# Fingerprint_lock_1_4.net
KiCad netlist of a schematic drawn in EAGLE
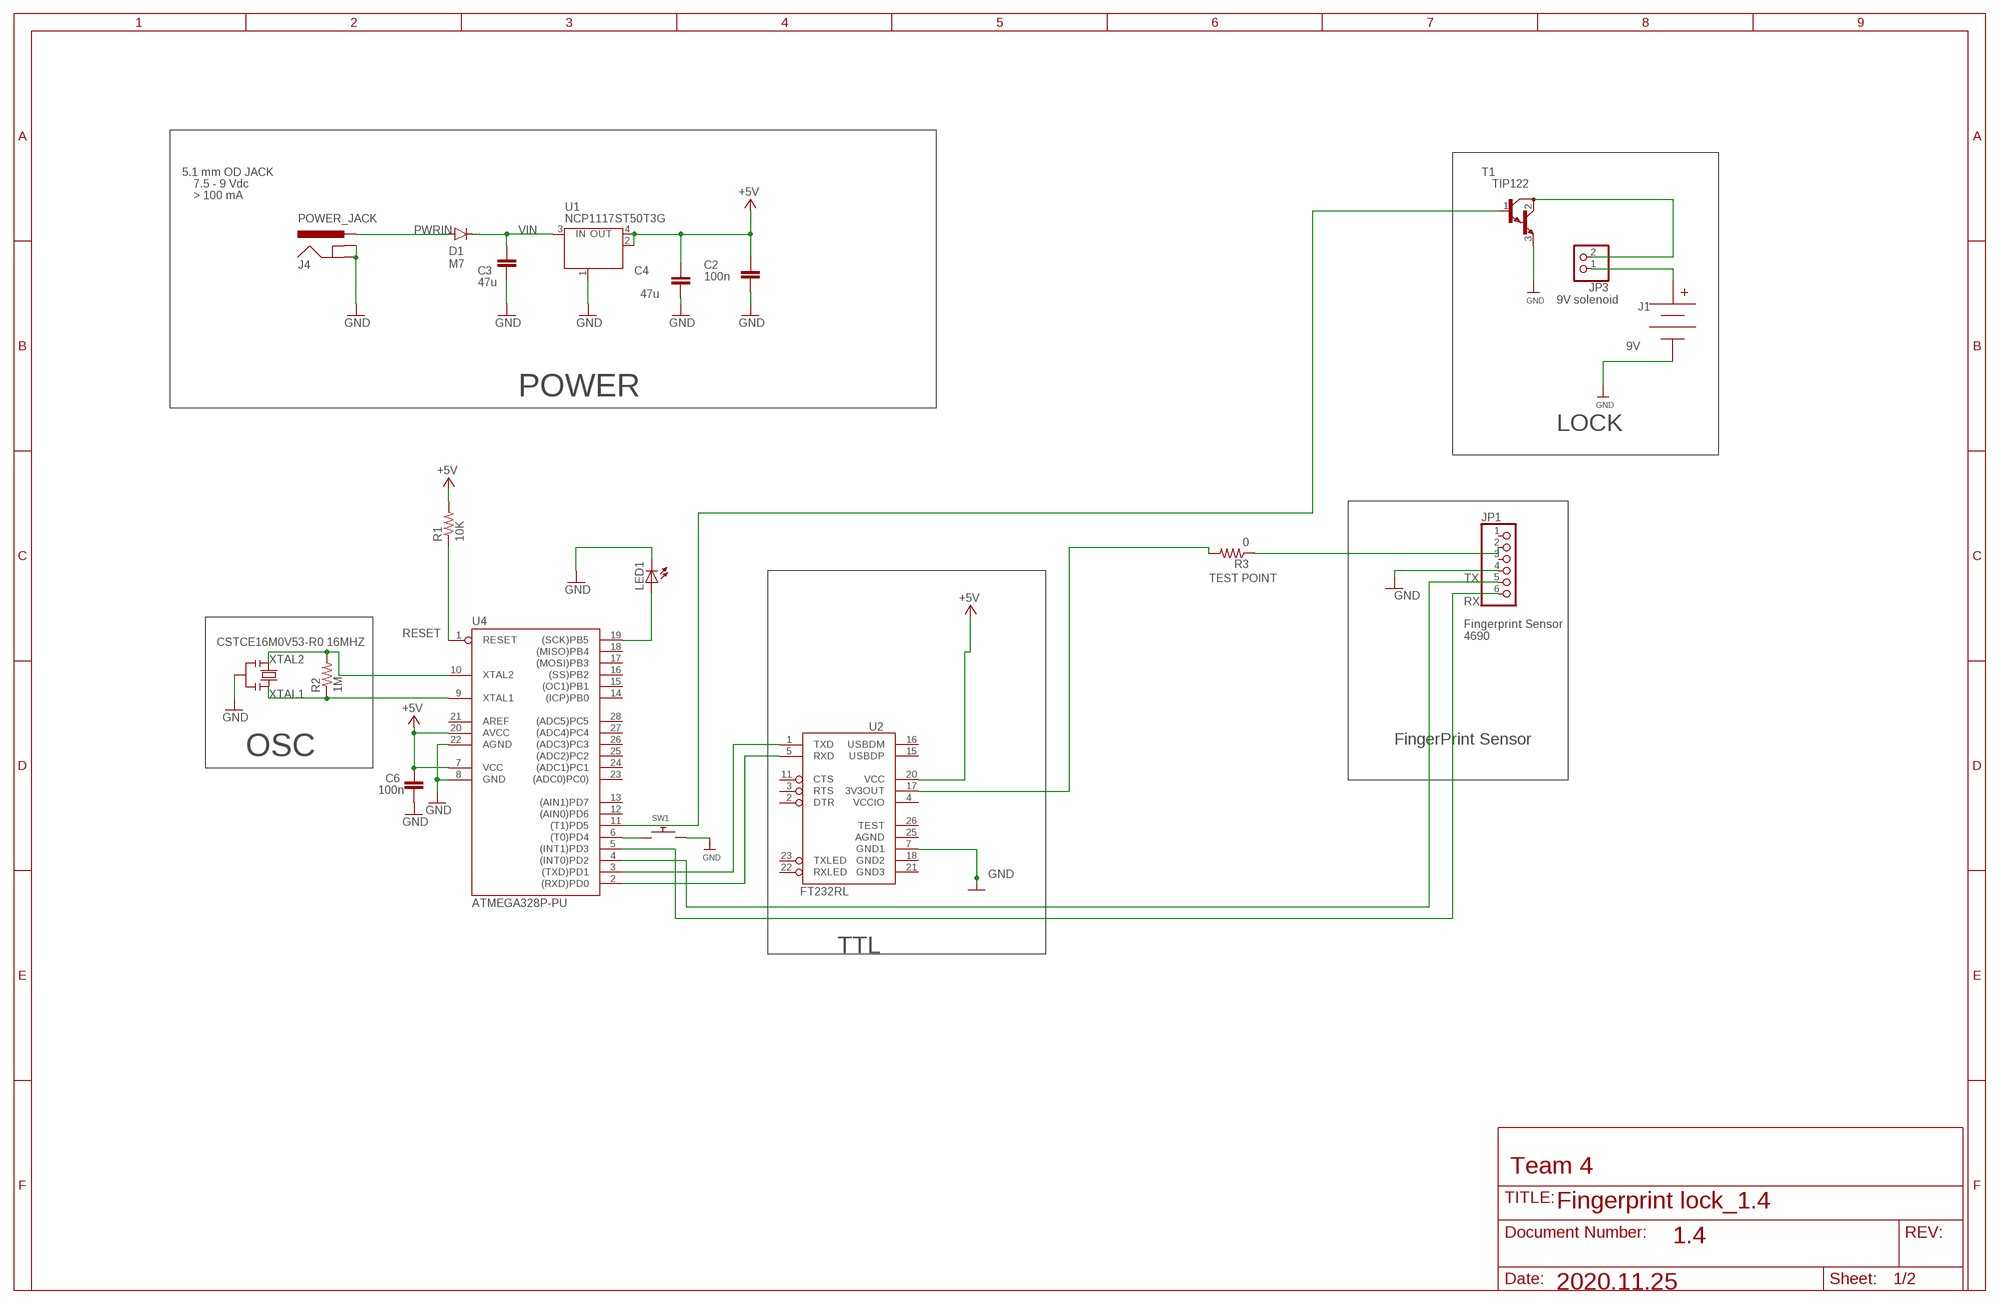
[diagram p0: schematic, sheet 1]

(export (version "E")
  (design (tool "Eeschema 10.0.6"))
  (components
    (comp (ref "C2")
      (value "100n")
      (footprint "eagle-import:C0805")
      (libsource (lib "eagle-import") (part "C-EUC0805"))
    )
    (comp (ref "C3")
      (value "47u")
      (footprint "eagle-import:C0805")
      (libsource (lib "eagle-import") (part "C-EUC0805"))
    )
    (comp (ref "C4")
      (value "47u")
      (footprint "eagle-import:C0805")
      (libsource (lib "eagle-import") (part "C-EUC0805"))
    )
    (comp (ref "C6")
      (value "100n")
      (footprint "eagle-import:C0805")
      (libsource (lib "eagle-import") (part "C-EUC0805"))
    )
    (comp (ref "D1")
      (value "M7")
      (footprint "eagle-import:SMB")
      (libsource (lib "eagle-import") (part "DIODE-SMB"))
    )
    (comp (ref "J1")
      (value "9V")
      (footprint "eagle-import:BC9VPC")
      (libsource (lib "eagle-import") (part "BC9VPC"))
    )
    (comp (ref "J4")
      (value "POWER_JACK")
      (footprint "eagle-import:POWER_JACK_PTH")
      (libsource (lib "eagle-import") (part "POWER_JACK"))
    )
    (comp (ref "JP1")
      (value "PINHD-1X6B")
      (footprint "eagle-import:1X06-BIG")
      (libsource (lib "eagle-import") (part "PINHD-1X6B"))
    )
    (comp (ref "JP3")
      (value "PINHD-1X2")
      (footprint "eagle-import:1X02")
      (libsource (lib "eagle-import") (part "PINHD-1X2"))
    )
    (comp (ref "LED1")
      (value "LEDB155")
      (footprint "eagle-import:Q62902-B155")
      (libsource (lib "eagle-import") (part "LEDB155"))
    )
    (comp (ref "R1")
      (value "10K")
      (footprint "eagle-import:R0805")
      (libsource (lib "eagle-import") (part "R-US_R0805"))
    )
    (comp (ref "R2")
      (value "1M")
      (footprint "eagle-import:R0805")
      (libsource (lib "eagle-import") (part "R-US_R0805"))
    )
    (comp (ref "R3")
      (value "0")
      (footprint "eagle-import:R0805")
      (libsource (lib "eagle-import") (part "R-US_R0805"))
    )
    (comp (ref "SW1")
      (value "SWITCH_PUSHBUTTONEVQ-PE")
      (footprint "eagle-import:TACT_PANA-EVQ")
      (libsource (lib "eagle-import") (part "SWITCH_PUSHBUTTONEVQ-PE"))
    )
    (comp (ref "T1")
      (value "TIP122")
      (footprint "eagle-import:TO220")
      (libsource (lib "eagle-import") (part "TIP122"))
    )
    (comp (ref "U1")
      (value "NCP1117ST50T3G")
      (footprint "eagle-import:SOT223")
      (libsource (lib "eagle-import") (part "MC33269ST-3.3T3"))
    )
    (comp (ref "U2")
      (value "FT232RL")
      (footprint "eagle-import:SSOP28DB")
      (libsource (lib "eagle-import") (part "FT232RL-BASICSSOP"))
    )
    (comp (ref "U4")
      (value "ATMEGA328P-PU")
      (footprint "eagle-import:DIL28-3")
      (libsource (lib "eagle-import") (part "ATMEGA328P-PU"))
    )
    (comp (ref "X1")
      (value "CSTCE16M0V53-R0 16MHZ")
      (footprint "eagle-import:RESONATOR")
      (libsource (lib "eagle-import") (part "RESONATORMU"))
    )
  )
  (nets
    (net (code "1") (name "+5V") (class "Default")
      (node (ref "C2") (pin "2") (pinfunction "2_2") (pintype "passive"))
      (node (ref "C4") (pin "2") (pinfunction "2_2") (pintype "passive"))
      (node (ref "C6") (pin "2") (pinfunction "2_2") (pintype "passive"))
      (node (ref "R1") (pin "2") (pinfunction "2_2") (pintype "passive"))
      (node (ref "U1") (pin "2") (pinfunction "OUT_2") (pintype "passive"))
      (node (ref "U1") (pin "4") (pinfunction "OUT_4") (pintype "passive"))
      (node (ref "U2") (pin "20") (pinfunction "VCC_20") (pintype "power_in"))
      (node (ref "U4") (pin "20") (pinfunction "AVCC_20") (pintype "power_in"))
      (node (ref "U4") (pin "7") (pinfunction "VCC_7") (pintype "power_in"))
    )
    (net (code "2") (name "AGND") (class "Default")
      (node (ref "U2") (pin "25") (pinfunction "AGND_25") (pintype "power_in"))
    )
    (net (code "3") (name "GND") (class "Default")
      (node (ref "C2") (pin "1") (pinfunction "1_1") (pintype "passive"))
      (node (ref "C3") (pin "1") (pinfunction "1_1") (pintype "passive"))
      (node (ref "C4") (pin "1") (pinfunction "1_1") (pintype "passive"))
      (node (ref "C6") (pin "1") (pinfunction "1_1") (pintype "passive"))
      (node (ref "J1") (pin "V-") (pinfunction "V-_V-") (pintype "bidirectional"))
      (node (ref "J4") (pin "GND") (pinfunction "GND_GND") (pintype "bidirectional"))
      (node (ref "J4") (pin "GNDBREAK") (pinfunction "GNDBREAK_GNDBREAK") (pintype "bidirectional"))
      (node (ref "JP1") (pin "4") (pinfunction "4_4") (pintype "passive"))
      (node (ref "LED1") (pin "K") (pinfunction "C_K") (pintype "passive"))
      (node (ref "SW1") (pin "P$2") (pinfunction "P$2_P$2") (pintype "passive"))
      (node (ref "T1") (pin "3") (pinfunction "E_3") (pintype "passive"))
      (node (ref "U1") (pin "1") (pinfunction "GND/ADJ_1") (pintype "input"))
      (node (ref "U2") (pin "7") (pinfunction "GND1_7") (pintype "power_in"))
      (node (ref "U4") (pin "22") (pinfunction "AGND_22") (pintype "power_in"))
      (node (ref "U4") (pin "8") (pinfunction "GND_8") (pintype "power_in"))
      (node (ref "X1") (pin "2") (pinfunction "2_2") (pintype "passive"))
    )
    (net (code "4") (name "GND2") (class "Default")
      (node (ref "U2") (pin "18") (pinfunction "GND2_18") (pintype "power_in"))
    )
    (net (code "5") (name "GND3") (class "Default")
      (node (ref "U2") (pin "21") (pinfunction "GND3_21") (pintype "power_in"))
    )
    (net (code "6") (name "Net-(J1-PadV+)") (class "Default")
      (node (ref "J1") (pin "V+") (pinfunction "V+_V+") (pintype "bidirectional"))
      (node (ref "JP3") (pin "1") (pinfunction "1_1") (pintype "passive"))
    )
    (net (code "7") (name "Net-(JP1-Pad2)") (class "Default")
      (node (ref "JP1") (pin "2") (pinfunction "2_2") (pintype "passive"))
      (node (ref "R3") (pin "1") (pinfunction "1_1") (pintype "passive"))
    )
    (net (code "8") (name "Net-(T1-B)") (class "Default")
      (node (ref "T1") (pin "1") (pinfunction "B_1") (pintype "passive"))
      (node (ref "U4") (pin "11") (pinfunction "(T1)PD5_11") (pintype "bidirectional"))
    )
    (net (code "9") (name "Net-(T1-C)") (class "Default")
      (node (ref "JP3") (pin "2") (pinfunction "2_2") (pintype "passive"))
      (node (ref "T1") (pin "2") (pinfunction "C_2") (pintype "passive"))
    )
    (net (code "10") (name "Net-(U2-3V3OUT)") (class "Default")
      (node (ref "R3") (pin "2") (pinfunction "2_2") (pintype "passive"))
      (node (ref "U2") (pin "17") (pinfunction "3V3OUT_17") (pintype "output"))
    )
    (net (code "11") (name "Net-(U2-RXD)") (class "Default")
      (node (ref "U2") (pin "5") (pinfunction "RXD_5") (pintype "input"))
      (node (ref "U4") (pin "2") (pinfunction "(RXD)PD0_2") (pintype "bidirectional"))
    )
    (net (code "12") (name "Net-(U2-TXD)") (class "Default")
      (node (ref "U2") (pin "1") (pinfunction "TXD_1") (pintype "output"))
      (node (ref "U4") (pin "3") (pinfunction "(TXD)PD1_3") (pintype "bidirectional"))
    )
    (net (code "13") (name "Net-(U4-(INT0)PD2)") (class "Default")
      (node (ref "JP1") (pin "5") (pinfunction "5_5") (pintype "passive"))
      (node (ref "U4") (pin "4") (pinfunction "(INT0)PD2_4") (pintype "bidirectional"))
    )
    (net (code "14") (name "Net-(U4-(INT1)PD3)") (class "Default")
      (node (ref "JP1") (pin "6") (pinfunction "6_6") (pintype "passive"))
      (node (ref "U4") (pin "5") (pinfunction "(INT1)PD3_5") (pintype "bidirectional"))
    )
    (net (code "15") (name "Net-(U4-(SCK)PB5)") (class "Default")
      (node (ref "LED1") (pin "A") (pinfunction "A_A") (pintype "passive"))
      (node (ref "U4") (pin "19") (pinfunction "(SCK)PB5_19") (pintype "bidirectional"))
    )
    (net (code "16") (name "Net-(U4-(T0)PD4)") (class "Default")
      (node (ref "SW1") (pin "P$1") (pinfunction "P$1_P$1") (pintype "passive"))
      (node (ref "U4") (pin "6") (pinfunction "(T0)PD4_6") (pintype "bidirectional"))
    )
    (net (code "17") (name "PWRIN") (class "Default")
      (node (ref "D1") (pin "A") (pinfunction "A_A") (pintype "passive"))
      (node (ref "J4") (pin "PWR") (pinfunction "PWR_PWR") (pintype "bidirectional"))
    )
    (net (code "18") (name "RESET") (class "Default")
      (node (ref "R1") (pin "1") (pinfunction "1_1") (pintype "passive"))
      (node (ref "U4") (pin "1") (pinfunction "RESET_1") (pintype "input"))
    )
    (net (code "19") (name "VCCIO") (class "Default")
      (node (ref "U2") (pin "4") (pinfunction "VCCIO_4") (pintype "power_in"))
    )
    (net (code "20") (name "VIN") (class "Default")
      (node (ref "C3") (pin "2") (pinfunction "2_2") (pintype "passive"))
      (node (ref "D1") (pin "C") (pinfunction "C_C") (pintype "passive"))
      (node (ref "U1") (pin "3") (pinfunction "IN_3") (pintype "input"))
    )
    (net (code "21") (name "XTAL1") (class "Default")
      (node (ref "R2") (pin "1") (pinfunction "1_1") (pintype "passive"))
      (node (ref "U4") (pin "9") (pinfunction "XTAL1_9") (pintype "bidirectional"))
      (node (ref "X1") (pin "3") (pinfunction "3_3") (pintype "passive"))
    )
    (net (code "22") (name "XTAL2") (class "Default")
      (node (ref "R2") (pin "2") (pinfunction "2_2") (pintype "passive"))
      (node (ref "U4") (pin "10") (pinfunction "XTAL2_10") (pintype "bidirectional"))
      (node (ref "X1") (pin "1") (pinfunction "1_1") (pintype "passive"))
    )
    (net (code "23") (name "unconnected-(JP1-Pad1)") (class "Default")
      (node (ref "JP1") (pin "1") (pinfunction "1_1") (pintype "passive"))
    )
    (net (code "24") (name "unconnected-(JP1-Pad3)") (class "Default")
      (node (ref "JP1") (pin "3") (pinfunction "3_3") (pintype "passive"))
    )
    (net (code "25") (name "unconnected-(U2-CTS-Pad11)") (class "Default")
      (node (ref "U2") (pin "11") (pinfunction "CTS_11") (pintype "bidirectional"))
    )
    (net (code "26") (name "unconnected-(U2-DTR-Pad2)") (class "Default")
      (node (ref "U2") (pin "2") (pinfunction "DTR_2") (pintype "bidirectional"))
    )
    (net (code "27") (name "unconnected-(U2-RTS-Pad3)") (class "Default")
      (node (ref "U2") (pin "3") (pinfunction "RTS_3") (pintype "bidirectional"))
    )
    (net (code "28") (name "unconnected-(U2-RXLED-Pad22)") (class "Default")
      (node (ref "U2") (pin "22") (pinfunction "RXLED_22") (pintype "bidirectional"))
    )
    (net (code "29") (name "unconnected-(U2-TEST-Pad26)") (class "Default")
      (node (ref "U2") (pin "26") (pinfunction "TEST_26") (pintype "input"))
    )
    (net (code "30") (name "unconnected-(U2-TXLED-Pad23)") (class "Default")
      (node (ref "U2") (pin "23") (pinfunction "TXLED_23") (pintype "bidirectional"))
    )
    (net (code "31") (name "unconnected-(U2-USBDM-Pad16)") (class "Default")
      (node (ref "U2") (pin "16") (pinfunction "USBDM_16") (pintype "bidirectional"))
    )
    (net (code "32") (name "unconnected-(U2-USBDP-Pad15)") (class "Default")
      (node (ref "U2") (pin "15") (pinfunction "USBDP_15") (pintype "bidirectional"))
    )
    (net (code "33") (name "unconnected-(U4-(ADC0)PC0)-Pad23)") (class "Default")
      (node (ref "U4") (pin "23") (pinfunction "(ADC0)PC0)_23") (pintype "bidirectional"))
    )
    (net (code "34") (name "unconnected-(U4-(ADC1)PC1-Pad24)") (class "Default")
      (node (ref "U4") (pin "24") (pinfunction "(ADC1)PC1_24") (pintype "bidirectional"))
    )
    (net (code "35") (name "unconnected-(U4-(ADC2)PC2-Pad25)") (class "Default")
      (node (ref "U4") (pin "25") (pinfunction "(ADC2)PC2_25") (pintype "bidirectional"))
    )
    (net (code "36") (name "unconnected-(U4-(ADC3)PC3-Pad26)") (class "Default")
      (node (ref "U4") (pin "26") (pinfunction "(ADC3)PC3_26") (pintype "bidirectional"))
    )
    (net (code "37") (name "unconnected-(U4-(ADC4)PC4-Pad27)") (class "Default")
      (node (ref "U4") (pin "27") (pinfunction "(ADC4)PC4_27") (pintype "bidirectional"))
    )
    (net (code "38") (name "unconnected-(U4-(ADC5)PC5-Pad28)") (class "Default")
      (node (ref "U4") (pin "28") (pinfunction "(ADC5)PC5_28") (pintype "bidirectional"))
    )
    (net (code "39") (name "unconnected-(U4-(AIN0)PD6-Pad12)") (class "Default")
      (node (ref "U4") (pin "12") (pinfunction "(AIN0)PD6_12") (pintype "bidirectional"))
    )
    (net (code "40") (name "unconnected-(U4-(AIN1)PD7-Pad13)") (class "Default")
      (node (ref "U4") (pin "13") (pinfunction "(AIN1)PD7_13") (pintype "bidirectional"))
    )
    (net (code "41") (name "unconnected-(U4-(ICP)PB0-Pad14)") (class "Default")
      (node (ref "U4") (pin "14") (pinfunction "(ICP)PB0_14") (pintype "bidirectional"))
    )
    (net (code "42") (name "unconnected-(U4-(MISO)PB4-Pad18)") (class "Default")
      (node (ref "U4") (pin "18") (pinfunction "(MISO)PB4_18") (pintype "bidirectional"))
    )
    (net (code "43") (name "unconnected-(U4-(MOSI)PB3-Pad17)") (class "Default")
      (node (ref "U4") (pin "17") (pinfunction "(MOSI)PB3_17") (pintype "bidirectional"))
    )
    (net (code "44") (name "unconnected-(U4-(OC1)PB1-Pad15)") (class "Default")
      (node (ref "U4") (pin "15") (pinfunction "(OC1)PB1_15") (pintype "bidirectional"))
    )
    (net (code "45") (name "unconnected-(U4-(SS)PB2-Pad16)") (class "Default")
      (node (ref "U4") (pin "16") (pinfunction "(SS)PB2_16") (pintype "bidirectional"))
    )
    (net (code "46") (name "unconnected-(U4-AREF-Pad21)") (class "Default")
      (node (ref "U4") (pin "21") (pinfunction "AREF_21") (pintype "passive"))
    )
  )
)
